# SimpleAstableMultivibrator.net
KiCad netlist of a schematic drawn in Altium Designer
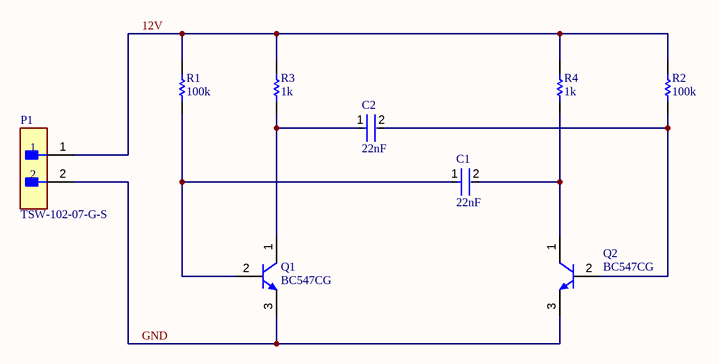
[diagram p0: SimpleAstableMultivibrator.SchDoc]

(export (version "E")
  (design (tool "Eeschema 10.0.6"))
  (components
    (comp (ref "C1")
      (value "22nF")
      (footprint "FP-C0603C-CF-IPC_A")
      (fields (field (name "Comment") "Capacitor 22nF +/-5% 16V 0603"))
      (libsource (lib "Muntakim Rahman") (part "b4654b650e69147ec39a6b967a45e02"))
    )
    (comp (ref "C2")
      (value "22nF")
      (footprint "FP-C0603C-CF-IPC_A")
      (fields (field (name "Comment") "Capacitor 22nF +/-5% 16V 0603"))
      (libsource (lib "Muntakim Rahman") (part "b4654b650e69147ec39a6b967a45e02"))
    )
    (comp (ref "P1")
      (value "TSW-102-07-G-S")
      (footprint "FP-TSW-102-07-G-S-MFG")
      (libsource (lib "Muntakim Rahman") (part "3bc925449376181038e59eaffc5286c"))
    )
    (comp (ref "Q1")
      (value "BC547CG")
      (footprint "ONSC-TO-92-3-29-11")
      (description "Small Signal Bipolar Transistor, 0.1A I(C), 45V V(BR)CEO, 1-Element, NPN, Silicon, TO-92")
      (libsource (lib "Muntakim Rahman") (part "ONSC-NPN-C1B2E3-3"))
    )
    (comp (ref "Q2")
      (value "BC547CG")
      (footprint "ONSC-TO-92-3-29-11")
      (description "Small Signal Bipolar Transistor, 0.1A I(C), 45V V(BR)CEO, 1-Element, NPN, Silicon, TO-92")
      (libsource (lib "Muntakim Rahman") (part "ONSC-NPN-C1B2E3-3"))
    )
    (comp (ref "R1")
      (value "100k")
      (footprint "RESC2013X70X40ML20T20")
      (fields
        (field (name "TOLERANCE") "5%")
        (field (name "POWER") "125mW")
        (field (name "Comment") "Resistor 100K +/-5% 0805 125 mW")
      )
      (libsource (lib "Muntakim Rahman") (part "RES"))
    )
    (comp (ref "R2")
      (value "100k")
      (footprint "RESC2013X70X40ML20T20")
      (fields
        (field (name "TOLERANCE") "5%")
        (field (name "POWER") "125mW")
        (field (name "Comment") "Resistor 100K +/-5% 0805 125 mW")
      )
      (libsource (lib "Muntakim Rahman") (part "RES"))
    )
    (comp (ref "R3")
      (value "1k")
      (footprint "RESC2013X70X40ML20T20")
      (fields
        (field (name "TOLERANCE") "5%")
        (field (name "POWER") "500mW")
        (field (name "Comment") "Resistor 1K +/-5% 0805 500 mW")
      )
      (libsource (lib "Muntakim Rahman") (part "RES"))
    )
    (comp (ref "R4")
      (value "1k")
      (footprint "RESC2013X70X40ML20T20")
      (fields
        (field (name "TOLERANCE") "5%")
        (field (name "POWER") "500mW")
        (field (name "Comment") "Resistor 1K +/-5% 0805 500 mW")
      )
      (libsource (lib "Muntakim Rahman") (part "RES"))
    )
  )
  (nets
    (net (code "1") (name "/12V") (class "Default")
      (node (ref "P1") (pin "1") (pinfunction "1_1") (pintype "passive"))
      (node (ref "R1") (pin "1") (pinfunction "1_1") (pintype "passive"))
      (node (ref "R2") (pin "1") (pinfunction "1_1") (pintype "passive"))
      (node (ref "R3") (pin "1") (pinfunction "1_1") (pintype "passive"))
      (node (ref "R4") (pin "1") (pinfunction "1_1") (pintype "passive"))
    )
    (net (code "2") (name "/GND") (class "Default")
      (node (ref "P1") (pin "2") (pinfunction "2_2") (pintype "passive"))
      (node (ref "Q1") (pin "3") (pinfunction "E_3") (pintype "passive"))
      (node (ref "Q2") (pin "3") (pinfunction "E_3") (pintype "passive"))
    )
    (net (code "3") (name "Net-(Q1-B)") (class "Default")
      (node (ref "C1") (pin "1") (pinfunction "1_1") (pintype "passive"))
      (node (ref "Q1") (pin "2") (pinfunction "B_2") (pintype "passive"))
      (node (ref "R1") (pin "2") (pinfunction "2_2") (pintype "passive"))
    )
    (net (code "4") (name "Net-(Q1-C)") (class "Default")
      (node (ref "C2") (pin "1") (pinfunction "1_1") (pintype "passive"))
      (node (ref "Q1") (pin "1") (pinfunction "C_1") (pintype "passive"))
      (node (ref "R3") (pin "2") (pinfunction "2_2") (pintype "passive"))
    )
    (net (code "5") (name "Net-(Q2-B)") (class "Default")
      (node (ref "C2") (pin "2") (pinfunction "2_2") (pintype "passive"))
      (node (ref "Q2") (pin "2") (pinfunction "B_2") (pintype "passive"))
      (node (ref "R2") (pin "2") (pinfunction "2_2") (pintype "passive"))
    )
    (net (code "6") (name "Net-(Q2-C)") (class "Default")
      (node (ref "C1") (pin "2") (pinfunction "2_2") (pintype "passive"))
      (node (ref "Q2") (pin "1") (pinfunction "C_1") (pintype "passive"))
      (node (ref "R4") (pin "2") (pinfunction "2_2") (pintype "passive"))
    )
  )
)
